# controller-right.net
KiCad netlist of a schematic drawn in EAGLE
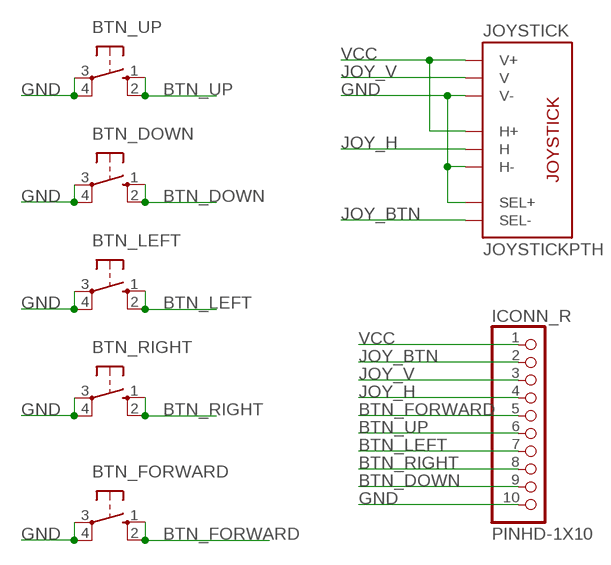
[diagram p0: schematic, sheet 1]

(export (version "E")
  (design (tool "Eeschema 10.0.6"))
  (components
    (comp (ref "BTN_DOWN")
      (value "40-XX-ROUND")
      (footprint "eagle-import:B3F-40XX-ROUND")
      (libsource (lib "eagle-import") (part "40-XX-ROUND"))
    )
    (comp (ref "BTN_FORWARD")
      (value "40-XX-ROUND")
      (footprint "eagle-import:B3F-40XX-ROUND")
      (libsource (lib "eagle-import") (part "40-XX-ROUND"))
    )
    (comp (ref "BTN_LEFT")
      (value "40-XX-ROUND")
      (footprint "eagle-import:B3F-40XX-ROUND")
      (libsource (lib "eagle-import") (part "40-XX-ROUND"))
    )
    (comp (ref "BTN_RIGHT")
      (value "40-XX-ROUND")
      (footprint "eagle-import:B3F-40XX-ROUND")
      (libsource (lib "eagle-import") (part "40-XX-ROUND"))
    )
    (comp (ref "BTN_UP")
      (value "40-XX-ROUND")
      (footprint "eagle-import:B3F-40XX-ROUND")
      (libsource (lib "eagle-import") (part "40-XX-ROUND"))
    )
    (comp (ref "ICONN_R")
      (value "PINHD-1X10")
      (footprint "eagle-import:1X10-BIG")
      (libsource (lib "eagle-import") (part "PINHD-1X10"))
    )
    (comp (ref "JOYSTICK")
      (value "JOYSTICKPTH")
      (footprint "eagle-import:JOYSTICK")
      (libsource (lib "eagle-import") (part "JOYSTICKPTH"))
    )
  )
  (nets
    (net (code "1") (name "/BTN_DOWN") (class "Default")
      (node (ref "BTN_DOWN") (pin "1") (pinfunction "S_1") (pintype "passive"))
      (node (ref "BTN_DOWN") (pin "2") (pinfunction "S1_2") (pintype "passive"))
      (node (ref "ICONN_R") (pin "9") (pinfunction "9_9") (pintype "passive"))
    )
    (net (code "2") (name "/BTN_FORWARD") (class "Default")
      (node (ref "BTN_FORWARD") (pin "1") (pinfunction "S_1") (pintype "passive"))
      (node (ref "BTN_FORWARD") (pin "2") (pinfunction "S1_2") (pintype "passive"))
      (node (ref "ICONN_R") (pin "5") (pinfunction "5_5") (pintype "passive"))
    )
    (net (code "3") (name "/BTN_LEFT") (class "Default")
      (node (ref "BTN_LEFT") (pin "1") (pinfunction "S_1") (pintype "passive"))
      (node (ref "BTN_LEFT") (pin "2") (pinfunction "S1_2") (pintype "passive"))
      (node (ref "ICONN_R") (pin "7") (pinfunction "7_7") (pintype "passive"))
    )
    (net (code "4") (name "/BTN_RIGHT") (class "Default")
      (node (ref "BTN_RIGHT") (pin "1") (pinfunction "S_1") (pintype "passive"))
      (node (ref "BTN_RIGHT") (pin "2") (pinfunction "S1_2") (pintype "passive"))
      (node (ref "ICONN_R") (pin "8") (pinfunction "8_8") (pintype "passive"))
    )
    (net (code "5") (name "/BTN_UP") (class "Default")
      (node (ref "BTN_UP") (pin "1") (pinfunction "S_1") (pintype "passive"))
      (node (ref "BTN_UP") (pin "2") (pinfunction "S1_2") (pintype "passive"))
      (node (ref "ICONN_R") (pin "6") (pinfunction "6_6") (pintype "passive"))
    )
    (net (code "6") (name "/GND") (class "Default")
      (node (ref "BTN_DOWN") (pin "3") (pinfunction "P_3") (pintype "passive"))
      (node (ref "BTN_DOWN") (pin "4") (pinfunction "P1_4") (pintype "passive"))
      (node (ref "BTN_FORWARD") (pin "3") (pinfunction "P_3") (pintype "passive"))
      (node (ref "BTN_FORWARD") (pin "4") (pinfunction "P1_4") (pintype "passive"))
      (node (ref "BTN_LEFT") (pin "3") (pinfunction "P_3") (pintype "passive"))
      (node (ref "BTN_LEFT") (pin "4") (pinfunction "P1_4") (pintype "passive"))
      (node (ref "BTN_RIGHT") (pin "3") (pinfunction "P_3") (pintype "passive"))
      (node (ref "BTN_RIGHT") (pin "4") (pinfunction "P1_4") (pintype "passive"))
      (node (ref "BTN_UP") (pin "3") (pinfunction "P_3") (pintype "passive"))
      (node (ref "BTN_UP") (pin "4") (pinfunction "P1_4") (pintype "passive"))
      (node (ref "ICONN_R") (pin "10") (pinfunction "10_10") (pintype "passive"))
      (node (ref "JOYSTICK") (pin "B1A") (pinfunction "SEL+_B1A") (pintype "bidirectional"))
      (node (ref "JOYSTICK") (pin "H3") (pinfunction "H-_H3") (pintype "bidirectional"))
      (node (ref "JOYSTICK") (pin "V3") (pinfunction "V-_V3") (pintype "bidirectional"))
    )
    (net (code "7") (name "/JOY_BTN") (class "Default")
      (node (ref "ICONN_R") (pin "2") (pinfunction "2_2") (pintype "passive"))
      (node (ref "JOYSTICK") (pin "B2A") (pinfunction "SEL-_B2A") (pintype "bidirectional"))
    )
    (net (code "8") (name "/JOY_H") (class "Default")
      (node (ref "ICONN_R") (pin "4") (pinfunction "4_4") (pintype "passive"))
      (node (ref "JOYSTICK") (pin "H2") (pinfunction "H_H2") (pintype "bidirectional"))
    )
    (net (code "9") (name "/JOY_V") (class "Default")
      (node (ref "ICONN_R") (pin "3") (pinfunction "3_3") (pintype "passive"))
      (node (ref "JOYSTICK") (pin "V2") (pinfunction "V_V2") (pintype "bidirectional"))
    )
    (net (code "10") (name "/VCC") (class "Default")
      (node (ref "ICONN_R") (pin "1") (pinfunction "1_1") (pintype "passive"))
      (node (ref "JOYSTICK") (pin "H1") (pinfunction "H+_H1") (pintype "bidirectional"))
      (node (ref "JOYSTICK") (pin "V1") (pinfunction "V+_V1") (pintype "bidirectional"))
    )
  )
)
